# adapter.net
KiCad netlist of a schematic drawn in EAGLE
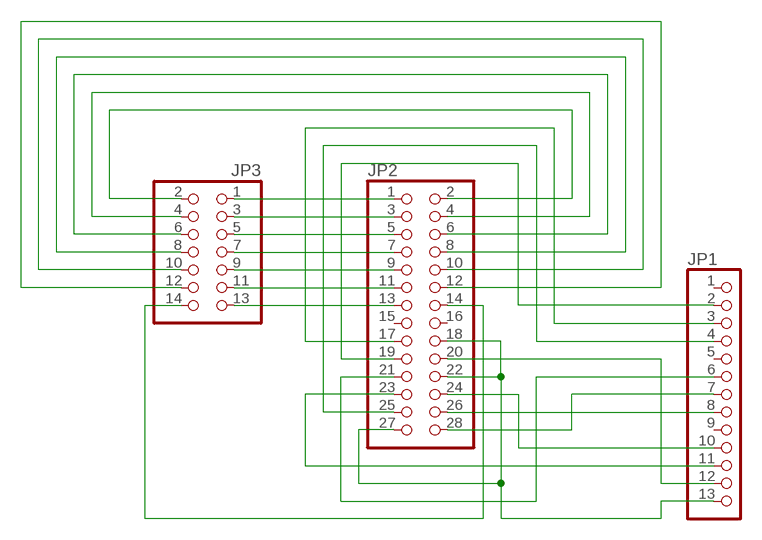
[diagram p0: schematic, sheet 1]

(export (version "E")
  (design (tool "Eeschema 10.0.6"))
  (components
    (comp (ref "JP1")
      (value "PINHD-1X13")
      (footprint "eagle-import:1X13")
      (libsource (lib "eagle-import") (part "PINHD-1X13"))
    )
    (comp (ref "JP2")
      (value "PINHD-2X14")
      (footprint "eagle-import:2X14")
      (libsource (lib "eagle-import") (part "PINHD-2X14"))
    )
    (comp (ref "JP3")
      (value "PINHD-2X7")
      (footprint "eagle-import:2X07")
      (libsource (lib "eagle-import") (part "PINHD-2X7"))
    )
  )
  (nets
    (net (code "1") (name "Net-(JP1-Pad2)") (class "Default")
      (node (ref "JP1") (pin "2") (pinfunction "2_2") (pintype "passive"))
      (node (ref "JP2") (pin "19") (pinfunction "19_19") (pintype "passive"))
    )
    (net (code "2") (name "Net-(JP1-Pad3)") (class "Default")
      (node (ref "JP1") (pin "3") (pinfunction "3_3") (pintype "passive"))
      (node (ref "JP2") (pin "17") (pinfunction "17_17") (pintype "passive"))
    )
    (net (code "3") (name "Net-(JP1-Pad4)") (class "Default")
      (node (ref "JP1") (pin "4") (pinfunction "4_4") (pintype "passive"))
      (node (ref "JP2") (pin "25") (pinfunction "25_25") (pintype "passive"))
    )
    (net (code "4") (name "Net-(JP1-Pad6)") (class "Default")
      (node (ref "JP1") (pin "6") (pinfunction "6_6") (pintype "passive"))
      (node (ref "JP2") (pin "21") (pinfunction "21_21") (pintype "passive"))
    )
    (net (code "5") (name "Net-(JP1-Pad7)") (class "Default")
      (node (ref "JP1") (pin "7") (pinfunction "7_7") (pintype "passive"))
      (node (ref "JP2") (pin "28") (pinfunction "28_28") (pintype "passive"))
    )
    (net (code "6") (name "Net-(JP1-Pad8)") (class "Default")
      (node (ref "JP1") (pin "8") (pinfunction "8_8") (pintype "passive"))
      (node (ref "JP2") (pin "26") (pinfunction "26_26") (pintype "passive"))
    )
    (net (code "7") (name "Net-(JP1-Pad10)") (class "Default")
      (node (ref "JP1") (pin "10") (pinfunction "10_10") (pintype "passive"))
      (node (ref "JP2") (pin "24") (pinfunction "24_24") (pintype "passive"))
    )
    (net (code "8") (name "Net-(JP1-Pad11)") (class "Default")
      (node (ref "JP1") (pin "11") (pinfunction "11_11") (pintype "passive"))
      (node (ref "JP2") (pin "23") (pinfunction "23_23") (pintype "passive"))
    )
    (net (code "9") (name "Net-(JP1-Pad12)") (class "Default")
      (node (ref "JP1") (pin "12") (pinfunction "12_12") (pintype "passive"))
      (node (ref "JP2") (pin "20") (pinfunction "20_20") (pintype "passive"))
    )
    (net (code "10") (name "Net-(JP1-Pad13)") (class "Default")
      (node (ref "JP1") (pin "13") (pinfunction "13_13") (pintype "passive"))
      (node (ref "JP2") (pin "18") (pinfunction "18_18") (pintype "passive"))
      (node (ref "JP2") (pin "22") (pinfunction "22_22") (pintype "passive"))
      (node (ref "JP2") (pin "27") (pinfunction "27_27") (pintype "passive"))
    )
    (net (code "11") (name "Net-(JP2-Pad1)") (class "Default")
      (node (ref "JP2") (pin "1") (pinfunction "1_1") (pintype "passive"))
      (node (ref "JP3") (pin "1") (pinfunction "1_1") (pintype "passive"))
    )
    (net (code "12") (name "Net-(JP2-Pad2)") (class "Default")
      (node (ref "JP2") (pin "2") (pinfunction "2_2") (pintype "passive"))
      (node (ref "JP3") (pin "2") (pinfunction "2_2") (pintype "passive"))
    )
    (net (code "13") (name "Net-(JP2-Pad3)") (class "Default")
      (node (ref "JP2") (pin "3") (pinfunction "3_3") (pintype "passive"))
      (node (ref "JP3") (pin "3") (pinfunction "3_3") (pintype "passive"))
    )
    (net (code "14") (name "Net-(JP2-Pad4)") (class "Default")
      (node (ref "JP2") (pin "4") (pinfunction "4_4") (pintype "passive"))
      (node (ref "JP3") (pin "4") (pinfunction "4_4") (pintype "passive"))
    )
    (net (code "15") (name "Net-(JP2-Pad5)") (class "Default")
      (node (ref "JP2") (pin "5") (pinfunction "5_5") (pintype "passive"))
      (node (ref "JP3") (pin "5") (pinfunction "5_5") (pintype "passive"))
    )
    (net (code "16") (name "Net-(JP2-Pad6)") (class "Default")
      (node (ref "JP2") (pin "6") (pinfunction "6_6") (pintype "passive"))
      (node (ref "JP3") (pin "6") (pinfunction "6_6") (pintype "passive"))
    )
    (net (code "17") (name "Net-(JP2-Pad7)") (class "Default")
      (node (ref "JP2") (pin "7") (pinfunction "7_7") (pintype "passive"))
      (node (ref "JP3") (pin "7") (pinfunction "7_7") (pintype "passive"))
    )
    (net (code "18") (name "Net-(JP2-Pad8)") (class "Default")
      (node (ref "JP2") (pin "8") (pinfunction "8_8") (pintype "passive"))
      (node (ref "JP3") (pin "8") (pinfunction "8_8") (pintype "passive"))
    )
    (net (code "19") (name "Net-(JP2-Pad9)") (class "Default")
      (node (ref "JP2") (pin "9") (pinfunction "9_9") (pintype "passive"))
      (node (ref "JP3") (pin "9") (pinfunction "9_9") (pintype "passive"))
    )
    (net (code "20") (name "Net-(JP2-Pad10)") (class "Default")
      (node (ref "JP2") (pin "10") (pinfunction "10_10") (pintype "passive"))
      (node (ref "JP3") (pin "10") (pinfunction "10_10") (pintype "passive"))
    )
    (net (code "21") (name "Net-(JP2-Pad11)") (class "Default")
      (node (ref "JP2") (pin "11") (pinfunction "11_11") (pintype "passive"))
      (node (ref "JP3") (pin "11") (pinfunction "11_11") (pintype "passive"))
    )
    (net (code "22") (name "Net-(JP2-Pad12)") (class "Default")
      (node (ref "JP2") (pin "12") (pinfunction "12_12") (pintype "passive"))
      (node (ref "JP3") (pin "12") (pinfunction "12_12") (pintype "passive"))
    )
    (net (code "23") (name "Net-(JP2-Pad13)") (class "Default")
      (node (ref "JP2") (pin "13") (pinfunction "13_13") (pintype "passive"))
      (node (ref "JP3") (pin "13") (pinfunction "13_13") (pintype "passive"))
    )
    (net (code "24") (name "Net-(JP2-Pad14)") (class "Default")
      (node (ref "JP2") (pin "14") (pinfunction "14_14") (pintype "passive"))
      (node (ref "JP3") (pin "14") (pinfunction "14_14") (pintype "passive"))
    )
    (net (code "25") (name "unconnected-(JP1-Pad1)") (class "Default")
      (node (ref "JP1") (pin "1") (pinfunction "1_1") (pintype "passive"))
    )
    (net (code "26") (name "unconnected-(JP1-Pad5)") (class "Default")
      (node (ref "JP1") (pin "5") (pinfunction "5_5") (pintype "passive"))
    )
    (net (code "27") (name "unconnected-(JP1-Pad9)") (class "Default")
      (node (ref "JP1") (pin "9") (pinfunction "9_9") (pintype "passive"))
    )
    (net (code "28") (name "unconnected-(JP2-Pad15)") (class "Default")
      (node (ref "JP2") (pin "15") (pinfunction "15_15") (pintype "passive"))
    )
    (net (code "29") (name "unconnected-(JP2-Pad16)") (class "Default")
      (node (ref "JP2") (pin "16") (pinfunction "16_16") (pintype "passive"))
    )
  )
)
